# 28_BoardPowerSupply_2.net
KiCad netlist of a schematic drawn in Altium Designer
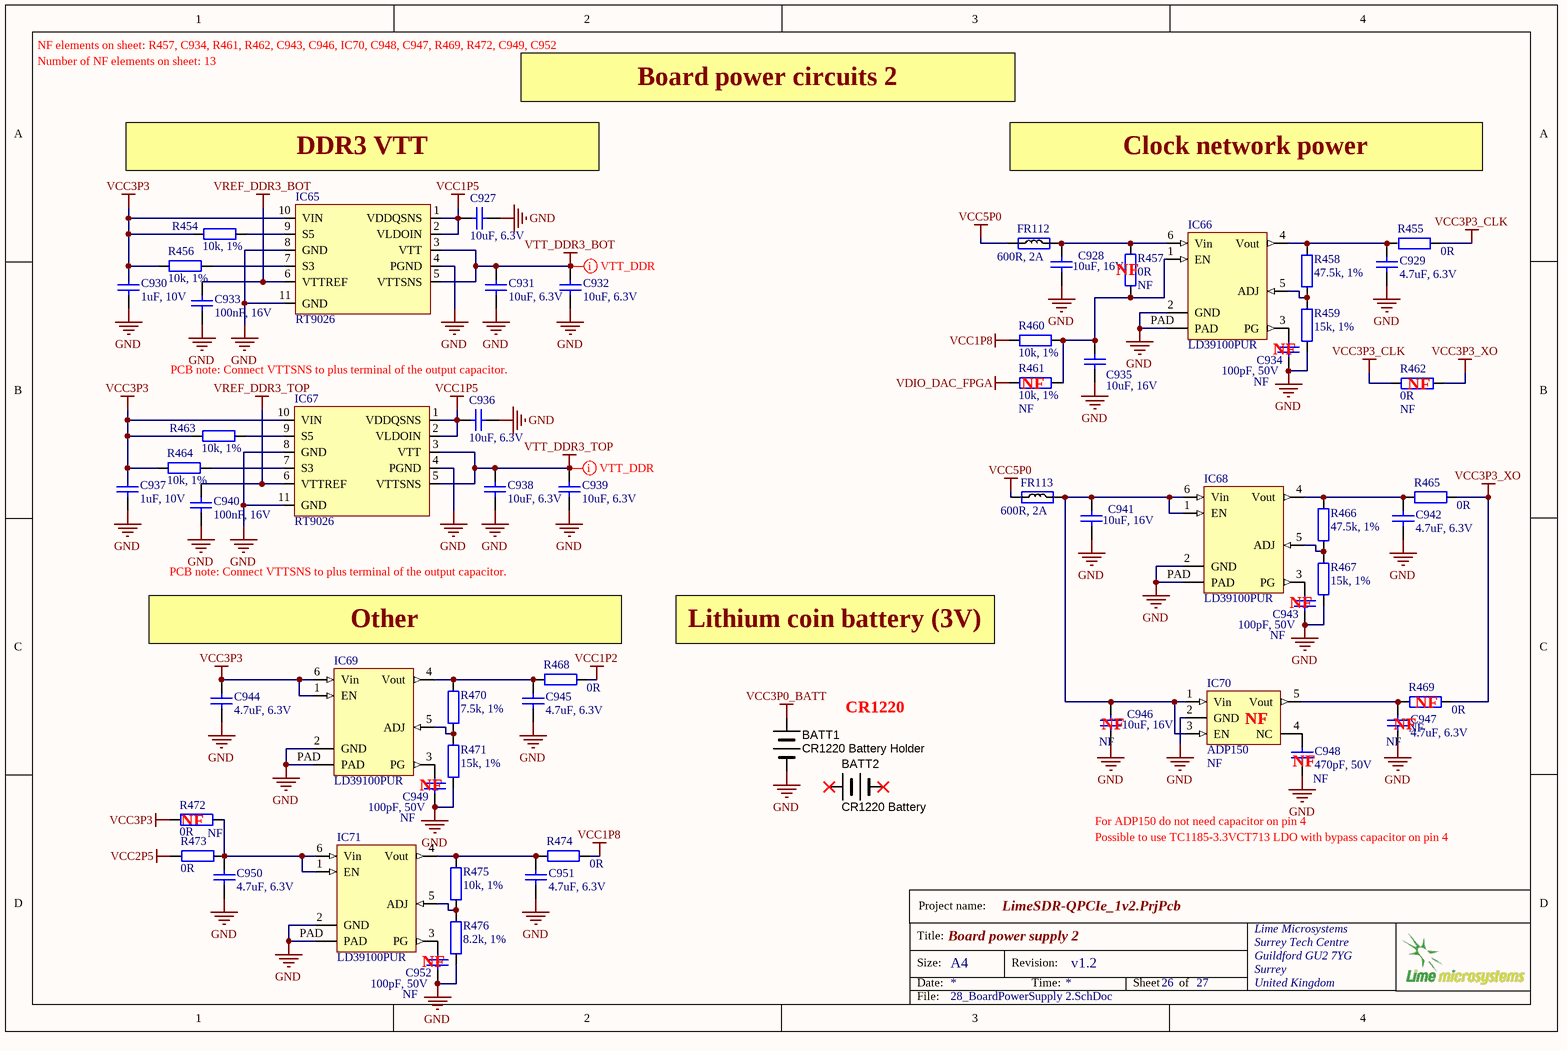
[diagram p0: 28_BoardPowerSupply 2.SchDoc]

(export (version "E")
  (design (tool "Eeschema 10.0.6"))
  (components
    (comp (ref "BATT1")
      (value "CR1220 Battery Holder")
      (footprint "CR1220_SMD_holder")
      (fields (field (name "MANUFACTURER") "MPD (Memory Protection Devices)"))
      (libsource (lib "LimeMicroAltiumLib_schLib") (part "CR1220_BATTERY_HOLDER"))
    )
    (comp (ref "BATT2")
      (value "CR1220 Battery")
      (fields (field (name "MANUFACTURER") "Panasonic - BSG"))
      (libsource (lib "LimeMicroAltiumLib_schLib") (part "CR1220_BATTERY"))
    )
    (comp (ref "C927")
      (value "10uF, 6.3V")
      (footprint "CAP0603")
      (fields (field (name "TOLERANCE") "±20%") (field (name "MANUFACTURER") "Yageo"))
      (libsource (lib "LimeFPGAboard_schLib") (part "Cap_0603"))
    )
    (comp (ref "C928")
      (value "10uF, 16V")
      (footprint "CAP0603")
      (fields (field (name "MANUFACTURER") "Yageo") (field (name "TOLERANCE") "±20%"))
      (libsource (lib "LimeMicroAltiumLib_schLib") (part "Cap_0603"))
    )
    (comp (ref "C929")
      (value "4.7uF, 6.3V")
      (footprint "CAP0402")
      (fields
        (field (name "MANUFACTURER") "Murata Electronics North America")
        (field (name "TOLERANCE") "±20%")
        (field (name "MANUFACTURER PART NUMBER") "GRM155R60J475ME87D")
      )
      (libsource (lib "LimeMicroAltiumLib_schLib") (part "Cap_0402"))
    )
    (comp (ref "C930")
      (value "1uF, 10V")
      (footprint "CAP0402")
      (fields (field (name "MANUFACTURER") "TDK"))
      (libsource (lib "LimeMicroAltiumLib_schLib") (part "Cap_0402"))
    )
    (comp (ref "C931")
      (value "10uF, 6.3V")
      (footprint "CAP0603")
      (fields (field (name "TOLERANCE") "±20%") (field (name "MANUFACTURER") "Yageo"))
      (libsource (lib "LimeFPGAboard_schLib") (part "Cap_0603"))
    )
    (comp (ref "C932")
      (value "10uF, 6.3V")
      (footprint "CAP0603")
      (fields (field (name "TOLERANCE") "±20%") (field (name "MANUFACTURER") "Yageo"))
      (libsource (lib "LimeFPGAboard_schLib") (part "Cap_0603"))
    )
    (comp (ref "C933")
      (value "100nF, 16V")
      (footprint "CAP0402")
      (fields
        (field (name "MANUFACTURER") "Murata Electronics")
        (field (name "TOLERANCE") "10 %")
        (field (name "MANUFACTURER PART NUMBER") "GRM155R71C104KA88D")
      )
      (libsource (lib "LimeMicroAltiumLib_schLib") (part "Cap_0402"))
    )
    (comp (ref "C934")
      (value "100pF, 50V")
      (footprint "CAP0402")
      (fields
        (field (name "ASSEMBLY INFO") "NF")
        (field (name "MANUFACTURER") "Yageo")
        (field (name "TOLERANCE") "±5%")
      )
      (libsource (lib "LimeMicroAltiumLib_schLib") (part "Cap_0402"))
    )
    (comp (ref "C935")
      (value "10uF, 16V")
      (footprint "CAP0603")
      (fields (field (name "MANUFACTURER") "Yageo") (field (name "TOLERANCE") "±20%"))
      (libsource (lib "LimeMicroAltiumLib_schLib") (part "Cap_0603"))
    )
    (comp (ref "C936")
      (value "10uF, 6.3V")
      (footprint "CAP0603")
      (fields (field (name "TOLERANCE") "±20%") (field (name "MANUFACTURER") "Yageo"))
      (libsource (lib "LimeFPGAboard_schLib") (part "Cap_0603"))
    )
    (comp (ref "C937")
      (value "1uF, 10V")
      (footprint "CAP0402")
      (fields (field (name "MANUFACTURER") "TDK"))
      (libsource (lib "LimeMicroAltiumLib_schLib") (part "Cap_0402"))
    )
    (comp (ref "C938")
      (value "10uF, 6.3V")
      (footprint "CAP0603")
      (fields (field (name "TOLERANCE") "±20%") (field (name "MANUFACTURER") "Yageo"))
      (libsource (lib "LimeFPGAboard_schLib") (part "Cap_0603"))
    )
    (comp (ref "C939")
      (value "10uF, 6.3V")
      (footprint "CAP0603")
      (fields (field (name "TOLERANCE") "±20%") (field (name "MANUFACTURER") "Yageo"))
      (libsource (lib "LimeFPGAboard_schLib") (part "Cap_0603"))
    )
    (comp (ref "C940")
      (value "100nF, 16V")
      (footprint "CAP0402")
      (fields
        (field (name "MANUFACTURER") "Murata Electronics")
        (field (name "TOLERANCE") "10 %")
        (field (name "MANUFACTURER PART NUMBER") "GRM155R71C104KA88D")
      )
      (libsource (lib "LimeMicroAltiumLib_schLib") (part "Cap_0402"))
    )
    (comp (ref "C941")
      (value "10uF, 16V")
      (footprint "CAP0603")
      (fields (field (name "MANUFACTURER") "Yageo") (field (name "TOLERANCE") "±20%"))
      (libsource (lib "LimeMicroAltiumLib_schLib") (part "Cap_0603"))
    )
    (comp (ref "C942")
      (value "4.7uF, 6.3V")
      (footprint "CAP0402")
      (fields
        (field (name "MANUFACTURER") "Murata Electronics North America")
        (field (name "TOLERANCE") "±20%")
        (field (name "MANUFACTURER PART NUMBER") "GRM155R60J475ME87D")
      )
      (libsource (lib "LimeMicroAltiumLib_schLib") (part "Cap_0402"))
    )
    (comp (ref "C943")
      (value "100pF, 50V")
      (footprint "CAP0402")
      (fields
        (field (name "ASSEMBLY INFO") "NF")
        (field (name "MANUFACTURER") "Yageo")
        (field (name "TOLERANCE") "±5%")
      )
      (libsource (lib "LimeMicroAltiumLib_schLib") (part "Cap_0402"))
    )
    (comp (ref "C944")
      (value "4.7uF, 6.3V")
      (footprint "CAP0402")
      (fields
        (field (name "MANUFACTURER") "Murata Electronics North America")
        (field (name "TOLERANCE") "±20%")
        (field (name "MANUFACTURER PART NUMBER") "GRM155R60J475ME87D")
      )
      (libsource (lib "LimeMicroAltiumLib_schLib") (part "Cap_0402"))
    )
    (comp (ref "C945")
      (value "4.7uF, 6.3V")
      (footprint "CAP0402")
      (fields
        (field (name "MANUFACTURER") "Murata Electronics North America")
        (field (name "TOLERANCE") "±20%")
        (field (name "MANUFACTURER PART NUMBER") "GRM155R60J475ME87D")
      )
      (libsource (lib "LimeMicroAltiumLib_schLib") (part "Cap_0402"))
    )
    (comp (ref "C946")
      (value "10uF, 16V")
      (footprint "CAP0603")
      (fields
        (field (name "ASSEMBLY INFO") "NF")
        (field (name "MANUFACTURER") "Yageo")
        (field (name "TOLERANCE") "±20%")
      )
      (libsource (lib "LimeMicroAltiumLib_schLib") (part "Cap_0603"))
    )
    (comp (ref "C947")
      (value "4.7uF, 6.3V")
      (footprint "CAP0402")
      (fields
        (field (name "ASSEMBLY INFO") "NF")
        (field (name "MANUFACTURER") "Murata Electronics North America")
        (field (name "TOLERANCE") "±20%")
        (field (name "MANUFACTURER PART NUMBER") "GRM155R60J475ME87D")
      )
      (libsource (lib "LimeMicroAltiumLib_schLib") (part "Cap_0402"))
    )
    (comp (ref "C948")
      (value "470pF, 50V")
      (footprint "CAP0402")
      (fields
        (field (name "MANUFACTURER PART NUMBER") "C1005C0G1H471J050BA")
        (field (name "TOLERANCE") "±5%")
        (field (name "MANUFACTURER") "TDK Corporation")
        (field (name "ASSEMBLY INFO") "NF")
      )
      (libsource (lib "LimeMicroAltiumLib_schLib") (part "Cap_0402"))
    )
    (comp (ref "C949")
      (value "100pF, 50V")
      (footprint "CAP0402")
      (fields
        (field (name "ASSEMBLY INFO") "NF")
        (field (name "MANUFACTURER") "Yageo")
        (field (name "TOLERANCE") "±5%")
      )
      (libsource (lib "LimeMicroAltiumLib_schLib") (part "Cap_0402"))
    )
    (comp (ref "C950")
      (value "4.7uF, 6.3V")
      (footprint "CAP0402")
      (fields
        (field (name "MANUFACTURER") "Murata Electronics North America")
        (field (name "TOLERANCE") "±20%")
        (field (name "MANUFACTURER PART NUMBER") "GRM155R60J475ME87D")
      )
      (libsource (lib "LimeMicroAltiumLib_schLib") (part "Cap_0402"))
    )
    (comp (ref "C951")
      (value "4.7uF, 6.3V")
      (footprint "CAP0402")
      (fields
        (field (name "MANUFACTURER") "Murata Electronics North America")
        (field (name "TOLERANCE") "±20%")
        (field (name "MANUFACTURER PART NUMBER") "GRM155R60J475ME87D")
      )
      (libsource (lib "LimeMicroAltiumLib_schLib") (part "Cap_0402"))
    )
    (comp (ref "C952")
      (value "100pF, 50V")
      (footprint "CAP0402")
      (fields
        (field (name "ASSEMBLY INFO") "NF")
        (field (name "MANUFACTURER") "Yageo")
        (field (name "TOLERANCE") "±5%")
      )
      (libsource (lib "LimeMicroAltiumLib_schLib") (part "Cap_0402"))
    )
    (comp (ref "FR112")
      (value "600R, 2A")
      (footprint "RES0805")
      (fields (field (name "MANUFACTURER") "TDK"))
      (libsource (lib "") (part "Ferrite_1"))
    )
    (comp (ref "FR113")
      (value "600R, 2A")
      (footprint "RES0805")
      (fields (field (name "MANUFACTURER") "TDK"))
      (libsource (lib "LimeMicroAltiumLib_schLib") (part "Ferrite"))
    )
    (comp (ref "IC65")
      (value "RT9026")
      (footprint "MSOP10")
      (fields (field (name "MANUFACTURER") "Richtek USA Inc."))
      (libsource (lib "LimeMicroAltiumLib_schLib") (part "RT9026"))
    )
    (comp (ref "IC66")
      (value "LD39100PUR")
      (footprint "LD39100PUR")
      (fields (field (name "MANUFACTURER") "STMicroelectronics"))
      (libsource (lib "LimeMicroAltiumLib_schLib") (part "LD39100PUR"))
    )
    (comp (ref "IC67")
      (value "RT9026")
      (footprint "MSOP10")
      (fields (field (name "MANUFACTURER") "Richtek USA Inc."))
      (libsource (lib "LimeMicroAltiumLib_schLib") (part "RT9026"))
    )
    (comp (ref "IC68")
      (value "LD39100PUR")
      (footprint "LD39100PUR")
      (fields (field (name "MANUFACTURER") "STMicroelectronics"))
      (libsource (lib "LimeMicroAltiumLib_schLib") (part "LD39100PUR"))
    )
    (comp (ref "IC69")
      (value "LD39100PUR")
      (footprint "LD39100PUR")
      (fields (field (name "MANUFACTURER") "STMicroelectronics"))
      (libsource (lib "LimeMicroAltiumLib_schLib") (part "LD39100PUR"))
    )
    (comp (ref "IC70")
      (value "ADP150")
      (footprint "SOT23-5")
      (fields (field (name "MANUFACTURER") "Analog Devices Inc.") (field (name "ASSEMBLY INFO") "NF"))
      (libsource (lib "LimeMicroAltiumLib_schLib") (part "ADP150"))
    )
    (comp (ref "IC71")
      (value "LD39100PUR")
      (footprint "LD39100PUR")
      (fields (field (name "MANUFACTURER") "STMicroelectronics"))
      (libsource (lib "LimeMicroAltiumLib_schLib") (part "LD39100PUR"))
    )
    (comp (ref "R454")
      (value "10k, 1%")
      (footprint "RES0402")
      (fields (field (name "MANUFACTURER") "Yageo") (field (name "TOLERANCE") "±1%"))
      (libsource (lib "LimeMicroAltiumLib_schLib") (part "Res_0402"))
    )
    (comp (ref "R455")
      (value "0R")
      (footprint "RES0402")
      (fields (field (name "MANUFACTURER") "Yageo") (field (name "TOLERANCE") "Jumper"))
      (libsource (lib "LimeMicroAltiumLib_schLib") (part "Res_0402"))
    )
    (comp (ref "R456")
      (value "10k, 1%")
      (footprint "RES0402")
      (fields (field (name "MANUFACTURER") "Yageo") (field (name "TOLERANCE") "±1%"))
      (libsource (lib "LimeMicroAltiumLib_schLib") (part "Res_0402"))
    )
    (comp (ref "R457")
      (value "0R")
      (footprint "RES0805")
      (fields
        (field (name "ASSEMBLY INFO") "NF")
        (field (name "MANUFACTURER") "Vishay Dale")
        (field (name "TOLERANCE") "Jumper")
      )
      (libsource (lib "LimeMicroAltiumLib_schLib") (part "Res_0402"))
    )
    (comp (ref "R458")
      (value "47.5k, 1%")
      (footprint "RES0402")
      (fields
        (field (name "MANUFACTURER PART NUMBER") "ERJ-2RKF4752X")
        (field (name "MANUFACTURER") "Panasonic Electronic Components")
        (field (name "TOLERANCE") "±1%")
      )
      (libsource (lib "LimeMicroAltiumLib_schLib") (part "Res_0402"))
    )
    (comp (ref "R459")
      (value "15k, 1%")
      (footprint "RES0402")
      (fields (field (name "TOLERANCE") "±1%") (field (name "MANUFACTURER") "Yageo"))
      (libsource (lib "LimeMicroAltiumLib_schLib") (part "Res_0402"))
    )
    (comp (ref "R460")
      (value "10k, 1%")
      (footprint "RES0402")
      (fields (field (name "MANUFACTURER") "Yageo") (field (name "TOLERANCE") "±1%"))
      (libsource (lib "LimeMicroAltiumLib_schLib") (part "Res_0402"))
    )
    (comp (ref "R461")
      (value "10k, 1%")
      (footprint "RES0402")
      (fields
        (field (name "ASSEMBLY INFO") "NF")
        (field (name "MANUFACTURER") "Yageo")
        (field (name "TOLERANCE") "±1%")
      )
      (libsource (lib "LimeMicroAltiumLib_schLib") (part "Res_0402"))
    )
    (comp (ref "R462")
      (value "0R")
      (footprint "RES0805")
      (fields
        (field (name "ASSEMBLY INFO") "NF")
        (field (name "MANUFACTURER") "Vishay Dale")
        (field (name "TOLERANCE") "Jumper")
      )
      (libsource (lib "LimeMicroAltiumLib_schLib") (part "Res_0402"))
    )
    (comp (ref "R463")
      (value "10k, 1%")
      (footprint "RES0402")
      (fields (field (name "MANUFACTURER") "Yageo") (field (name "TOLERANCE") "±1%"))
      (libsource (lib "LimeMicroAltiumLib_schLib") (part "Res_0402"))
    )
    (comp (ref "R464")
      (value "10k, 1%")
      (footprint "RES0402")
      (fields (field (name "MANUFACTURER") "Yageo") (field (name "TOLERANCE") "±1%"))
      (libsource (lib "LimeMicroAltiumLib_schLib") (part "Res_0402"))
    )
    (comp (ref "R465")
      (value "0R")
      (footprint "RES0402")
      (fields (field (name "MANUFACTURER") "Yageo") (field (name "TOLERANCE") "Jumper"))
      (libsource (lib "LimeMicroAltiumLib_schLib") (part "Res_0402"))
    )
    (comp (ref "R466")
      (value "47.5k, 1%")
      (footprint "RES0402")
      (fields
        (field (name "MANUFACTURER PART NUMBER") "ERJ-2RKF4752X")
        (field (name "MANUFACTURER") "Panasonic Electronic Components")
        (field (name "TOLERANCE") "±1%")
      )
      (libsource (lib "LimeMicroAltiumLib_schLib") (part "Res_0402"))
    )
    (comp (ref "R467")
      (value "15k, 1%")
      (footprint "RES0402")
      (fields (field (name "TOLERANCE") "±1%") (field (name "MANUFACTURER") "Yageo"))
      (libsource (lib "LimeMicroAltiumLib_schLib") (part "Res_0402"))
    )
    (comp (ref "R468")
      (value "0R")
      (footprint "RES0402")
      (fields (field (name "MANUFACTURER") "Yageo") (field (name "TOLERANCE") "Jumper"))
      (libsource (lib "LimeMicroAltiumLib_schLib") (part "Res_0402"))
    )
    (comp (ref "R469")
      (value "0R")
      (footprint "RES0402")
      (fields
        (field (name "ASSEMBLY INFO") "NF")
        (field (name "MANUFACTURER") "Yageo")
        (field (name "TOLERANCE") "Jumper")
      )
      (libsource (lib "LimeMicroAltiumLib_schLib") (part "Res_0402"))
    )
    (comp (ref "R470")
      (value "7.5k, 1%")
      (footprint "RES0402")
      (fields
        (field (name "MANUFACTURER") "Yageo")
        (field (name "TOLERANCE") "±1%")
        (field (name "MANUFACTURER PART NUMBER") "RC0402FR-077K5L")
      )
      (libsource (lib "LimeMicroAltiumLib_schLib") (part "Res_0402"))
    )
    (comp (ref "R471")
      (value "15k, 1%")
      (footprint "RES0402")
      (fields (field (name "TOLERANCE") "±1%") (field (name "MANUFACTURER") "Yageo"))
      (libsource (lib "LimeMicroAltiumLib_schLib") (part "Res_0402"))
    )
    (comp (ref "R472")
      (value "0R")
      (footprint "RES0805")
      (fields
        (field (name "ASSEMBLY INFO") "NF")
        (field (name "MANUFACTURER") "Vishay Dale")
        (field (name "TOLERANCE") "Jumper")
      )
      (libsource (lib "LimeMicroAltiumLib_schLib") (part "Res_0402"))
    )
    (comp (ref "R473")
      (value "0R")
      (footprint "RES0402")
      (fields (field (name "MANUFACTURER") "Yageo") (field (name "TOLERANCE") "Jumper"))
      (libsource (lib "LimeMicroAltiumLib_schLib") (part "Res_0402"))
    )
    (comp (ref "R474")
      (value "0R")
      (footprint "RES0402")
      (fields (field (name "MANUFACTURER") "Yageo") (field (name "TOLERANCE") "Jumper"))
      (libsource (lib "LimeMicroAltiumLib_schLib") (part "Res_0402"))
    )
    (comp (ref "R475")
      (value "10k, 1%")
      (footprint "RES0402")
      (fields (field (name "MANUFACTURER") "Yageo") (field (name "TOLERANCE") "±1%"))
      (libsource (lib "LimeMicroAltiumLib_schLib") (part "Res_0402"))
    )
    (comp (ref "R476")
      (value "8.2k, 1%")
      (footprint "RES0402")
      (fields (field (name "MANUFACTURER") "Yageo") (field (name "TOLERANCE") "±1%"))
      (libsource (lib "LimeMicroAltiumLib_schLib") (part "Res_0402"))
    )
  )
  (nets
    (net (code "1") (name "GND") (class "Default")
      (node (ref "BATT1") (pin "NEGATIVE") (pintype "passive"))
      (node (ref "C927") (pin "1") (pinfunction "1_1") (pintype "passive"))
      (node (ref "C928") (pin "1") (pinfunction "1_1") (pintype "passive"))
      (node (ref "C929") (pin "1") (pinfunction "1_1") (pintype "passive"))
      (node (ref "C930") (pin "1") (pinfunction "1_1") (pintype "passive"))
      (node (ref "C931") (pin "1") (pinfunction "1_1") (pintype "passive"))
      (node (ref "C932") (pin "1") (pinfunction "1_1") (pintype "passive"))
      (node (ref "C933") (pin "2") (pinfunction "2_2") (pintype "passive"))
      (node (ref "C934") (pin "1") (pinfunction "1_1") (pintype "passive"))
      (node (ref "C935") (pin "1") (pinfunction "1_1") (pintype "passive"))
      (node (ref "C936") (pin "1") (pinfunction "1_1") (pintype "passive"))
      (node (ref "C937") (pin "1") (pinfunction "1_1") (pintype "passive"))
      (node (ref "C938") (pin "1") (pinfunction "1_1") (pintype "passive"))
      (node (ref "C939") (pin "1") (pinfunction "1_1") (pintype "passive"))
      (node (ref "C940") (pin "2") (pinfunction "2_2") (pintype "passive"))
      (node (ref "C941") (pin "1") (pinfunction "1_1") (pintype "passive"))
      (node (ref "C942") (pin "1") (pinfunction "1_1") (pintype "passive"))
      (node (ref "C943") (pin "1") (pinfunction "1_1") (pintype "passive"))
      (node (ref "C944") (pin "1") (pinfunction "1_1") (pintype "passive"))
      (node (ref "C945") (pin "1") (pinfunction "1_1") (pintype "passive"))
      (node (ref "C946") (pin "1") (pinfunction "1_1") (pintype "passive"))
      (node (ref "C947") (pin "1") (pinfunction "1_1") (pintype "passive"))
      (node (ref "C948") (pin "2") (pinfunction "2_2") (pintype "passive"))
      (node (ref "C949") (pin "1") (pinfunction "1_1") (pintype "passive"))
      (node (ref "C950") (pin "1") (pinfunction "1_1") (pintype "passive"))
      (node (ref "C951") (pin "1") (pinfunction "1_1") (pintype "passive"))
      (node (ref "C952") (pin "1") (pinfunction "1_1") (pintype "passive"))
      (node (ref "IC65") (pin "11") (pinfunction "GND_11") (pintype "passive"))
      (node (ref "IC65") (pin "4") (pinfunction "PGND_4") (pintype "passive"))
      (node (ref "IC65") (pin "8") (pinfunction "GND_8") (pintype "passive"))
      (node (ref "IC66") (pin "2") (pinfunction "GND_2") (pintype "passive"))
      (node (ref "IC66") (pin "PAD") (pinfunction "PAD_PAD") (pintype "passive"))
      (node (ref "IC67") (pin "11") (pinfunction "GND_11") (pintype "passive"))
      (node (ref "IC67") (pin "4") (pinfunction "PGND_4") (pintype "passive"))
      (node (ref "IC67") (pin "8") (pinfunction "GND_8") (pintype "passive"))
      (node (ref "IC68") (pin "2") (pinfunction "GND_2") (pintype "passive"))
      (node (ref "IC68") (pin "PAD") (pinfunction "PAD_PAD") (pintype "passive"))
      (node (ref "IC69") (pin "2") (pinfunction "GND_2") (pintype "passive"))
      (node (ref "IC69") (pin "PAD") (pinfunction "PAD_PAD") (pintype "passive"))
      (node (ref "IC70") (pin "2") (pinfunction "GND_2") (pintype "passive"))
      (node (ref "IC71") (pin "2") (pinfunction "GND_2") (pintype "passive"))
      (node (ref "IC71") (pin "PAD") (pinfunction "PAD_PAD") (pintype "passive"))
      (node (ref "R459") (pin "1") (pinfunction "1_1") (pintype "passive"))
      (node (ref "R467") (pin "1") (pinfunction "1_1") (pintype "passive"))
      (node (ref "R471") (pin "1") (pinfunction "1_1") (pintype "passive"))
      (node (ref "R476") (pin "1") (pinfunction "1_1") (pintype "passive"))
    )
    (net (code "2") (name "Net-(IC65-S3)") (class "Default")
      (node (ref "IC65") (pin "7") (pinfunction "S3_7") (pintype "passive"))
      (node (ref "R456") (pin "2") (pinfunction "2_2") (pintype "passive"))
    )
    (net (code "3") (name "Net-(IC65-S5)") (class "Default")
      (node (ref "IC65") (pin "9") (pinfunction "S5_9") (pintype "passive"))
      (node (ref "R454") (pin "2") (pinfunction "2_2") (pintype "passive"))
    )
    (net (code "4") (name "Net-(IC66-ADJ)") (class "Default")
      (node (ref "IC66") (pin "5") (pinfunction "ADJ_5") (pintype "input"))
      (node (ref "R458") (pin "1") (pinfunction "1_1") (pintype "passive"))
      (node (ref "R459") (pin "2") (pinfunction "2_2") (pintype "passive"))
    )
    (net (code "5") (name "Net-(IC66-EN)") (class "Default")
      (node (ref "C935") (pin "2") (pinfunction "2_2") (pintype "passive"))
      (node (ref "IC66") (pin "1") (pinfunction "EN_1") (pintype "input"))
      (node (ref "R457") (pin "2") (pinfunction "2_2") (pintype "passive"))
      (node (ref "R460") (pin "2") (pinfunction "2_2") (pintype "passive"))
      (node (ref "R461") (pin "2") (pinfunction "2_2") (pintype "passive"))
    )
    (net (code "6") (name "Net-(IC66-PG)") (class "Default")
      (node (ref "C934") (pin "2") (pinfunction "2_2") (pintype "passive"))
      (node (ref "IC66") (pin "3") (pinfunction "PG_3") (pintype "output"))
    )
    (net (code "7") (name "Net-(IC66-Vin)") (class "Default")
      (node (ref "C928") (pin "2") (pinfunction "2_2") (pintype "passive"))
      (node (ref "FR112") (pin "2") (pinfunction "2_2") (pintype "passive"))
      (node (ref "IC66") (pin "6") (pinfunction "Vin_6") (pintype "input"))
      (node (ref "R457") (pin "1") (pinfunction "1_1") (pintype "passive"))
    )
    (net (code "8") (name "Net-(IC66-Vout)") (class "Default")
      (node (ref "C929") (pin "2") (pinfunction "2_2") (pintype "passive"))
      (node (ref "IC66") (pin "4") (pinfunction "Vout_4") (pintype "output"))
      (node (ref "R455") (pin "2") (pinfunction "2_2") (pintype "passive"))
      (node (ref "R458") (pin "2") (pinfunction "2_2") (pintype "passive"))
    )
    (net (code "9") (name "Net-(IC67-S3)") (class "Default")
      (node (ref "IC67") (pin "7") (pinfunction "S3_7") (pintype "passive"))
      (node (ref "R464") (pin "2") (pinfunction "2_2") (pintype "passive"))
    )
    (net (code "10") (name "Net-(IC67-S5)") (class "Default")
      (node (ref "IC67") (pin "9") (pinfunction "S5_9") (pintype "passive"))
      (node (ref "R463") (pin "2") (pinfunction "2_2") (pintype "passive"))
    )
    (net (code "11") (name "Net-(IC68-ADJ)") (class "Default")
      (node (ref "IC68") (pin "5") (pinfunction "ADJ_5") (pintype "input"))
      (node (ref "R466") (pin "1") (pinfunction "1_1") (pintype "passive"))
      (node (ref "R467") (pin "2") (pinfunction "2_2") (pintype "passive"))
    )
    (net (code "12") (name "Net-(IC68-EN)") (class "Default")
      (node (ref "C941") (pin "2") (pinfunction "2_2") (pintype "passive"))
      (node (ref "C946") (pin "2") (pinfunction "2_2") (pintype "passive"))
      (node (ref "FR113") (pin "2") (pinfunction "2_2") (pintype "passive"))
      (node (ref "IC68") (pin "1") (pinfunction "EN_1") (pintype "input"))
      (node (ref "IC68") (pin "6") (pinfunction "Vin_6") (pintype "input"))
      (node (ref "IC70") (pin "1") (pinfunction "Vin_1") (pintype "input"))
      (node (ref "IC70") (pin "3") (pinfunction "EN_3") (pintype "input"))
    )
    (net (code "13") (name "Net-(IC68-PG)") (class "Default")
      (node (ref "C943") (pin "2") (pinfunction "2_2") (pintype "passive"))
      (node (ref "IC68") (pin "3") (pinfunction "PG_3") (pintype "output"))
    )
    (net (code "14") (name "Net-(IC68-Vout)") (class "Default")
      (node (ref "C942") (pin "2") (pinfunction "2_2") (pintype "passive"))
      (node (ref "IC68") (pin "4") (pinfunction "Vout_4") (pintype "output"))
      (node (ref "R465") (pin "2") (pinfunction "2_2") (pintype "passive"))
      (node (ref "R466") (pin "2") (pinfunction "2_2") (pintype "passive"))
    )
    (net (code "15") (name "Net-(IC69-ADJ)") (class "Default")
      (node (ref "IC69") (pin "5") (pinfunction "ADJ_5") (pintype "input"))
      (node (ref "R470") (pin "1") (pinfunction "1_1") (pintype "passive"))
      (node (ref "R471") (pin "2") (pinfunction "2_2") (pintype "passive"))
    )
    (net (code "16") (name "Net-(IC69-PG)") (class "Default")
      (node (ref "C949") (pin "2") (pinfunction "2_2") (pintype "passive"))
      (node (ref "IC69") (pin "3") (pinfunction "PG_3") (pintype "output"))
    )
    (net (code "17") (name "Net-(IC69-Vout)") (class "Default")
      (node (ref "C945") (pin "2") (pinfunction "2_2") (pintype "passive"))
      (node (ref "IC69") (pin "4") (pinfunction "Vout_4") (pintype "output"))
      (node (ref "R468") (pin "2") (pinfunction "2_2") (pintype "passive"))
      (node (ref "R470") (pin "2") (pinfunction "2_2") (pintype "passive"))
    )
    (net (code "18") (name "Net-(IC70-NC)") (class "Default")
      (node (ref "C948") (pin "1") (pinfunction "1_1") (pintype "passive"))
      (node (ref "IC70") (pin "4") (pinfunction "NC_4") (pintype "passive"))
    )
    (net (code "19") (name "Net-(IC70-Vout)") (class "Default")
      (node (ref "C947") (pin "2") (pinfunction "2_2") (pintype "passive"))
      (node (ref "IC70") (pin "5") (pinfunction "Vout_5") (pintype "output"))
      (node (ref "R469") (pin "2") (pinfunction "2_2") (pintype "passive"))
    )
    (net (code "20") (name "Net-(IC71-ADJ)") (class "Default")
      (node (ref "IC71") (pin "5") (pinfunction "ADJ_5") (pintype "input"))
      (node (ref "R475") (pin "1") (pinfunction "1_1") (pintype "passive"))
      (node (ref "R476") (pin "2") (pinfunction "2_2") (pintype "passive"))
    )
    (net (code "21") (name "Net-(IC71-EN)") (class "Default")
      (node (ref "C950") (pin "2") (pinfunction "2_2") (pintype "passive"))
      (node (ref "IC71") (pin "1") (pinfunction "EN_1") (pintype "input"))
      (node (ref "IC71") (pin "6") (pinfunction "Vin_6") (pintype "input"))
      (node (ref "R472") (pin "1") (pinfunction "1_1") (pintype "passive"))
      (node (ref "R473") (pin "1") (pinfunction "1_1") (pintype "passive"))
    )
    (net (code "22") (name "Net-(IC71-PG)") (class "Default")
      (node (ref "C952") (pin "2") (pinfunction "2_2") (pintype "passive"))
      (node (ref "IC71") (pin "3") (pinfunction "PG_3") (pintype "output"))
    )
    (net (code "23") (name "Net-(IC71-Vout)") (class "Default")
      (node (ref "C951") (pin "2") (pinfunction "2_2") (pintype "passive"))
      (node (ref "IC71") (pin "4") (pinfunction "Vout_4") (pintype "output"))
      (node (ref "R474") (pin "2") (pinfunction "2_2") (pintype "passive"))
      (node (ref "R475") (pin "2") (pinfunction "2_2") (pintype "passive"))
    )
    (net (code "24") (name "VCC1P2") (class "Default")
      (node (ref "R468") (pin "1") (pinfunction "1_1") (pintype "passive"))
    )
    (net (code "25") (name "VCC1P5") (class "Default")
      (node (ref "C927") (pin "2") (pinfunction "2_2") (pintype "passive"))
      (node (ref "C936") (pin "2") (pinfunction "2_2") (pintype "passive"))
      (node (ref "IC65") (pin "1") (pinfunction "VDDQSNS_1") (pintype "passive"))
      (node (ref "IC65") (pin "2") (pinfunction "VLDOIN_2") (pintype "passive"))
      (node (ref "IC67") (pin "1") (pinfunction "VDDQSNS_1") (pintype "passive"))
      (node (ref "IC67") (pin "2") (pinfunction "VLDOIN_2") (pintype "passive"))
    )
    (net (code "26") (name "VCC1P8") (class "Default")
      (node (ref "R460") (pin "1") (pinfunction "1_1") (pintype "passive"))
      (node (ref "R474") (pin "1") (pinfunction "1_1") (pintype "passive"))
    )
    (net (code "27") (name "VCC2P5") (class "Default")
      (node (ref "R473") (pin "2") (pinfunction "2_2") (pintype "passive"))
    )
    (net (code "28") (name "VCC3P0_BATT") (class "Default")
      (node (ref "BATT1") (pin "POSITIVE") (pintype "passive"))
    )
    (net (code "29") (name "VCC3P3") (class "Default")
      (node (ref "C930") (pin "2") (pinfunction "2_2") (pintype "passive"))
      (node (ref "C937") (pin "2") (pinfunction "2_2") (pintype "passive"))
      (node (ref "C944") (pin "2") (pinfunction "2_2") (pintype "passive"))
      (node (ref "IC65") (pin "10") (pinfunction "VIN_10") (pintype "passive"))
      (node (ref "IC67") (pin "10") (pinfunction "VIN_10") (pintype "passive"))
      (node (ref "IC69") (pin "1") (pinfunction "EN_1") (pintype "input"))
      (node (ref "IC69") (pin "6") (pinfunction "Vin_6") (pintype "input"))
      (node (ref "R454") (pin "1") (pinfunction "1_1") (pintype "passive"))
      (node (ref "R456") (pin "1") (pinfunction "1_1") (pintype "passive"))
      (node (ref "R463") (pin "1") (pinfunction "1_1") (pintype "passive"))
      (node (ref "R464") (pin "1") (pinfunction "1_1") (pintype "passive"))
      (node (ref "R472") (pin "2") (pinfunction "2_2") (pintype "passive"))
    )
    (net (code "30") (name "VCC3P3_CLK") (class "Default")
      (node (ref "R455") (pin "1") (pinfunction "1_1") (pintype "passive"))
      (node (ref "R462") (pin "1") (pinfunction "1_1") (pintype "passive"))
    )
    (net (code "31") (name "VCC3P3_XO") (class "Default")
      (node (ref "R462") (pin "2") (pinfunction "2_2") (pintype "passive"))
      (node (ref "R465") (pin "1") (pinfunction "1_1") (pintype "passive"))
      (node (ref "R469") (pin "1") (pinfunction "1_1") (pintype "passive"))
    )
    (net (code "32") (name "VCC5P0") (class "Default")
      (node (ref "FR112") (pin "1") (pinfunction "1_1") (pintype "passive"))
      (node (ref "FR113") (pin "1") (pinfunction "1_1") (pintype "passive"))
    )
    (net (code "33") (name "VDIO_DAC_FPGA") (class "Default")
      (node (ref "R461") (pin "1") (pinfunction "1_1") (pintype "passive"))
    )
    (net (code "34") (name "VREF_DDR3_BOT") (class "Default")
      (node (ref "C933") (pin "1") (pinfunction "1_1") (pintype "passive"))
      (node (ref "IC65") (pin "6") (pinfunction "VTTREF_6") (pintype "passive"))
    )
    (net (code "35") (name "VREF_DDR3_TOP") (class "Default")
      (node (ref "C940") (pin "1") (pinfunction "1_1") (pintype "passive"))
      (node (ref "IC67") (pin "6") (pinfunction "VTTREF_6") (pintype "passive"))
    )
    (net (code "36") (name "VTT_DDR3_BOT") (class "Default")
      (node (ref "C931") (pin "2") (pinfunction "2_2") (pintype "passive"))
      (node (ref "C932") (pin "2") (pinfunction "2_2") (pintype "passive"))
      (node (ref "IC65") (pin "3") (pinfunction "VTT_3") (pintype "passive"))
      (node (ref "IC65") (pin "5") (pinfunction "VTTSNS_5") (pintype "passive"))
    )
    (net (code "37") (name "VTT_DDR3_TOP") (class "Default")
      (node (ref "C938") (pin "2") (pinfunction "2_2") (pintype "passive"))
      (node (ref "C939") (pin "2") (pinfunction "2_2") (pintype "passive"))
      (node (ref "IC67") (pin "3") (pinfunction "VTT_3") (pintype "passive"))
      (node (ref "IC67") (pin "5") (pinfunction "VTTSNS_5") (pintype "passive"))
    )
    (net (code "38") (name "unconnected-(BATT2-PadNEGATIVE)") (class "Default")
      (node (ref "BATT2") (pin "NEGATIVE") (pintype "passive+no_connect"))
    )
    (net (code "39") (name "unconnected-(BATT2-PadPOSITIVE)") (class "Default")
      (node (ref "BATT2") (pin "POSITIVE") (pintype "passive+no_connect"))
    )
  )
)
